# main_pcb.net
KiCad netlist of a schematic drawn in Altium Designer
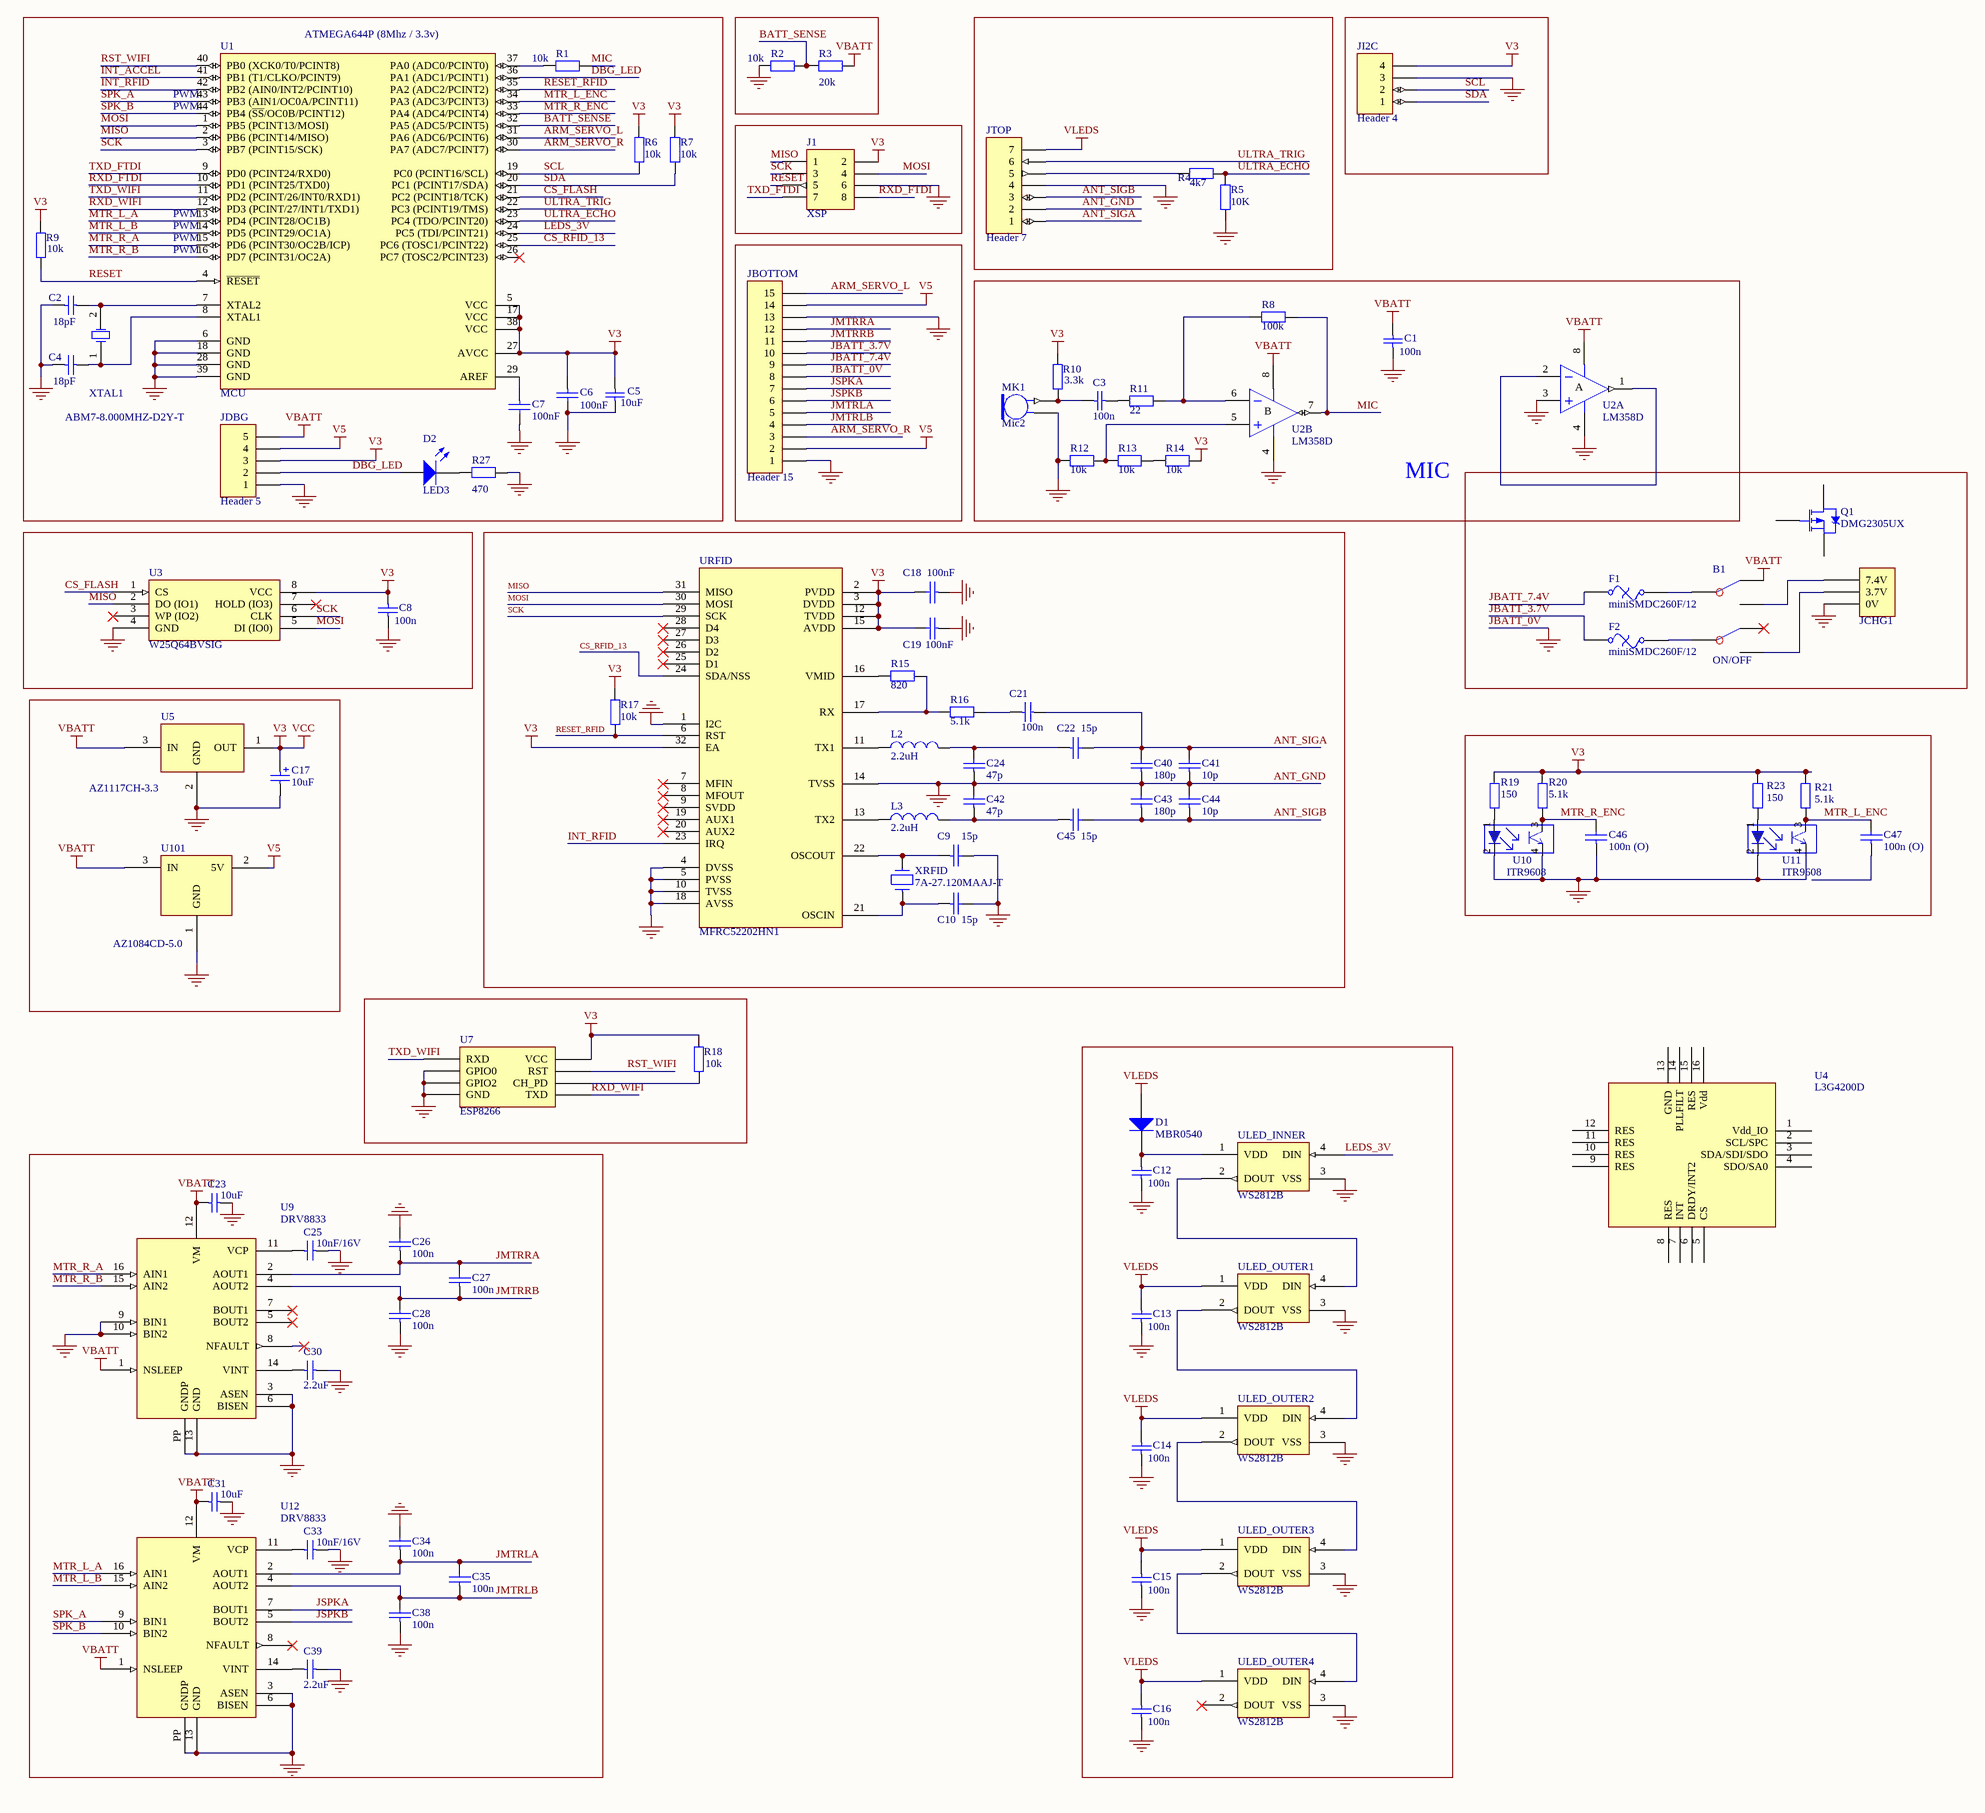
[diagram p0: main_pcb.SchDoc]

(export (version "E")
  (design (tool "Eeschema 10.0.6"))
  (components
    (comp (ref "B1") (value "ON/OFF") (footprint "KGPS22F03") (libsource (lib "*") (part "Component_1")))
    (comp (ref "C1")
      (value "100n")
      (footprint "CAPC1608N")
      (description "Capacitor")
      (libsource (lib "*") (part "Cap"))
    )
    (comp (ref "C2")
      (value "18pF")
      (footprint "CAPC1608N")
      (description "Capacitor")
      (libsource (lib "*") (part "Cap"))
    )
    (comp (ref "C3")
      (value "100n")
      (footprint "CAPC1608N")
      (description "Capacitor")
      (libsource (lib "") (part "Cap_1"))
    )
    (comp (ref "C4")
      (value "18pF")
      (footprint "CAPC1608N")
      (description "Capacitor")
      (libsource (lib "*") (part "Cap"))
    )
    (comp (ref "C5")
      (value "10uF")
      (footprint "CAPC3216L")
      (description "Capacitor")
      (libsource (lib "*") (part "Cap"))
    )
    (comp (ref "C6")
      (value "100nF")
      (footprint "CAPC1608N")
      (description "Capacitor")
      (libsource (lib "*") (part "CAP"))
    )
    (comp (ref "C7")
      (value "100nF")
      (footprint "CAPC1608N")
      (description "Capacitor")
      (libsource (lib "*") (part "CAP"))
    )
    (comp (ref "C8")
      (value "100n")
      (footprint "CAPC1608N")
      (description "Capacitor")
      (libsource (lib "*") (part "Cap"))
    )
    (comp (ref "C9")
      (value "15p")
      (footprint "CAPC1608N")
      (description "Capacitor")
      (libsource (lib "*") (part "CAP"))
    )
    (comp (ref "C10")
      (value "15p")
      (footprint "CAPC1608N")
      (description "Capacitor")
      (libsource (lib "*") (part "CAP"))
    )
    (comp (ref "C12")
      (value "100n")
      (footprint "CAPC1608N")
      (description "Capacitor")
      (libsource (lib "*") (part "Cap"))
    )
    (comp (ref "C13")
      (value "100n")
      (footprint "CAPC1608N")
      (description "Capacitor")
      (libsource (lib "*") (part "Cap"))
    )
    (comp (ref "C14")
      (value "100n")
      (footprint "CAPC1608N")
      (description "Capacitor")
      (libsource (lib "*") (part "Cap"))
    )
    (comp (ref "C15")
      (value "100n")
      (footprint "CAPC1608N")
      (description "Capacitor")
      (libsource (lib "*") (part "Cap"))
    )
    (comp (ref "C16")
      (value "100n")
      (footprint "CAPC1608N")
      (description "Capacitor")
      (libsource (lib "*") (part "Cap"))
    )
    (comp (ref "C17")
      (value "10uF")
      (footprint "CAPC2012N")
      (description "Polarized Capacitor (Axial)")
      (libsource (lib "*") (part "Cap Pol2"))
    )
    (comp (ref "C18")
      (value "100nF")
      (footprint "CAPC1608N")
      (description "Capacitor")
      (libsource (lib "*") (part "CAP"))
    )
    (comp (ref "C19")
      (value "100nF")
      (footprint "CAPC1608N")
      (description "Capacitor")
      (libsource (lib "*") (part "CAP"))
    )
    (comp (ref "C21")
      (value "100n")
      (footprint "CAPC1608N")
      (description "Capacitor")
      (libsource (lib "*") (part "Cap"))
    )
    (comp (ref "C22")
      (value "15p")
      (footprint "CAPC1608N")
      (description "Capacitor")
      (libsource (lib "*") (part "CAP"))
    )
    (comp (ref "C23")
      (value "10uF")
      (footprint "CAPC3216L")
      (description "Capacitor")
      (libsource (lib "*") (part "Cap"))
    )
    (comp (ref "C24")
      (value "47p")
      (footprint "CAPC1608N")
      (description "Capacitor")
      (libsource (lib "*") (part "CAP"))
    )
    (comp (ref "C25")
      (value "10nF/16V")
      (footprint "CAPC2012N")
      (description "Capacitor")
      (libsource (lib "*") (part "Cap"))
    )
    (comp (ref "C26")
      (value "100n")
      (footprint "CAPC1608N")
      (description "Capacitor")
      (libsource (lib "*") (part "CAP"))
    )
    (comp (ref "C27")
      (value "100n")
      (footprint "CAPC1608N")
      (description "Capacitor")
      (libsource (lib "*") (part "CAP"))
    )
    (comp (ref "C28")
      (value "100n")
      (footprint "CAPC1608N")
      (description "Capacitor")
      (libsource (lib "*") (part "CAP"))
    )
    (comp (ref "C30")
      (value "2.2uF")
      (footprint "CAPC2012N")
      (description "Capacitor")
      (libsource (lib "*") (part "Cap"))
    )
    (comp (ref "C31")
      (value "10uF")
      (footprint "CAPC3216L")
      (description "Capacitor")
      (libsource (lib "*") (part "Cap"))
    )
    (comp (ref "C33")
      (value "10nF/16V")
      (footprint "CAPC2012N")
      (description "Capacitor")
      (libsource (lib "*") (part "Cap"))
    )
    (comp (ref "C34")
      (value "100n")
      (footprint "CAPC1608N")
      (description "Capacitor")
      (libsource (lib "*") (part "CAP"))
    )
    (comp (ref "C35")
      (value "100n")
      (footprint "CAPC1608N")
      (description "Capacitor")
      (libsource (lib "*") (part "CAP"))
    )
    (comp (ref "C38")
      (value "100n")
      (footprint "CAPC1608N")
      (description "Capacitor")
      (libsource (lib "*") (part "CAP"))
    )
    (comp (ref "C39")
      (value "2.2uF")
      (footprint "CAPC2012N")
      (description "Capacitor")
      (libsource (lib "*") (part "Cap"))
    )
    (comp (ref "C40")
      (value "180p")
      (footprint "CAPC1608N")
      (description "Capacitor")
      (libsource (lib "*") (part "CAP"))
    )
    (comp (ref "C41")
      (value "10p")
      (footprint "CAPC1608N")
      (description "Capacitor")
      (libsource (lib "*") (part "CAP"))
    )
    (comp (ref "C42")
      (value "47p")
      (footprint "CAPC1608N")
      (description "Capacitor")
      (libsource (lib "*") (part "CAP"))
    )
    (comp (ref "C43")
      (value "180p")
      (footprint "CAPC1608N")
      (description "Capacitor")
      (libsource (lib "*") (part "CAP"))
    )
    (comp (ref "C44")
      (value "10p")
      (footprint "CAPC1608N")
      (description "Capacitor")
      (libsource (lib "*") (part "CAP"))
    )
    (comp (ref "C45")
      (value "15p")
      (footprint "CAPC1608N")
      (description "Capacitor")
      (libsource (lib "*") (part "CAP"))
    )
    (comp (ref "C46")
      (value "100n (O)")
      (footprint "CAPC1608N")
      (description "Capacitor")
      (libsource (lib "*") (part "CAP"))
    )
    (comp (ref "C47")
      (value "100n (O)")
      (footprint "CAPC1608N")
      (description "Capacitor")
      (libsource (lib "*") (part "CAP"))
    )
    (comp (ref "D1")
      (value "MBR0540")
      (footprint "SOD123/X.85")
      (description "Default Diode")
      (libsource (lib "Miscellaneous Devices") (part "Diode"))
    )
    (comp (ref "D2")
      (value "LED3")
      (footprint "CAPC1608N")
      (description "Typical BLUE SiC LED")
      (libsource (lib "Miscellaneous Devices") (part "LED3"))
    )
    (comp (ref "F1")
      (value "miniSMDC260F/12")
      (footprint "miniSMDC260F/12")
      (description "Thermal Fuse")
      (libsource (lib "Miscellaneous Devices") (part "Fuse Thermal"))
    )
    (comp (ref "F2")
      (value "miniSMDC260F/12")
      (footprint "miniSMDC260F/12")
      (description "Thermal Fuse")
      (libsource (lib "Miscellaneous Devices") (part "Fuse Thermal"))
    )
    (comp (ref "J1")
      (value "XSP")
      (footprint "HDR2X4H")
      (description "Header, 4-Pin, Dual row, Right Angle")
      (libsource (lib "Miscellaneous Connectors") (part "Header 4X2H"))
    )
    (comp (ref "JBOTTOM")
      (value "Header 15")
      (footprint "B15B-XH-A")
      (description "Header, 15-Pin")
      (libsource (lib "Miscellaneous Connectors") (part "Header 15"))
    )
    (comp (ref "JCHG1")
      (value "Charger")
      (footprint "S3B-XH-A(LF)(SN)")
      (libsource (lib "components") (part "BATTCON"))
    )
    (comp (ref "JDBG")
      (value "Header 5")
      (footprint "HDR1X5")
      (description "Header, 5-Pin")
      (libsource (lib "Miscellaneous Connectors") (part "Header 5"))
    )
    (comp (ref "JI2C")
      (value "Header 4")
      (footprint "HDR1X4")
      (description "Header, 4-Pin")
      (libsource (lib "Miscellaneous Connectors") (part "Header 4"))
    )
    (comp (ref "JTOP")
      (value "Header 7")
      (footprint "S7B-XH-A")
      (description "Header, 7-Pin")
      (libsource (lib "Miscellaneous Connectors") (part "Header 7"))
    )
    (comp (ref "L2")
      (value "2.2uH")
      (footprint "INDC1608N")
      (description "Inductor")
      (libsource (lib "Miscellaneous Devices") (part "Inductor"))
    )
    (comp (ref "L3")
      (value "2.2uH")
      (footprint "INDC1608N")
      (description "Inductor")
      (libsource (lib "Miscellaneous Devices") (part "Inductor"))
    )
    (comp (ref "MK1")
      (value "Mic2")
      (footprint "electret_6mm")
      (description "Microphone")
      (libsource (lib "*") (part "Mic2"))
    )
    (comp (ref "Q1")
      (value "DMG2305UX")
      (footprint "DMG2305UX-13")
      (libsource (lib "components") (part "DMG2305UX"))
    )
    (comp (ref "R1")
      (value "10k")
      (footprint "RESC1608N")
      (description "Resistor")
      (libsource (lib "") (part "Res2_2"))
    )
    (comp (ref "R2")
      (value "10k")
      (footprint "RESC1608N")
      (description "Resistor")
      (libsource (lib "") (part "Res2_2"))
    )
    (comp (ref "R3")
      (value "20k")
      (footprint "RESC1608N")
      (description "Resistor")
      (libsource (lib "") (part "Res2_2"))
    )
    (comp (ref "R4")
      (value "4k7")
      (footprint "RESC1608N")
      (description "Resistor")
      (fields (field (name "Comment") "10k"))
      (libsource (lib "") (part "Res2_3"))
    )
    (comp (ref "R5")
      (value "10K")
      (footprint "RESC1608N")
      (description "Resistor")
      (libsource (lib "") (part "Res2_1"))
    )
    (comp (ref "R6")
      (value "10k")
      (footprint "RESC1608N")
      (description "Resistor")
      (libsource (lib "*") (part "Res2"))
    )
    (comp (ref "R7")
      (value "10k")
      (footprint "RESC1608N")
      (description "Resistor")
      (libsource (lib "*") (part "Res2"))
    )
    (comp (ref "R8")
      (value "100k")
      (footprint "RESC1608N")
      (description "Resistor")
      (libsource (lib "") (part "Res2_2"))
    )
    (comp (ref "R9")
      (value "10k")
      (footprint "RESC1608N")
      (description "Resistor")
      (libsource (lib "") (part "Res2_1"))
    )
    (comp (ref "R10")
      (value "3.3k")
      (footprint "RESC1608N")
      (description "Resistor")
      (libsource (lib "") (part "Res2_1"))
    )
    (comp (ref "R11")
      (value "22")
      (footprint "RESC1608N")
      (description "Resistor")
      (libsource (lib "") (part "Res2_2"))
    )
    (comp (ref "R12")
      (value "10k")
      (footprint "RESC1608N")
      (description "Resistor")
      (libsource (lib "") (part "Res2_2"))
    )
    (comp (ref "R13")
      (value "10k")
      (footprint "RESC1608N")
      (description "Resistor")
      (libsource (lib "") (part "Res2_2"))
    )
    (comp (ref "R14")
      (value "10k")
      (footprint "RESC1608N")
      (description "Resistor")
      (libsource (lib "") (part "Res2_2"))
    )
    (comp (ref "R15")
      (value "820")
      (footprint "RESC1608N")
      (description "Resistor")
      (libsource (lib "") (part "Res2_3"))
    )
    (comp (ref "R16")
      (value "5.1k")
      (footprint "RESC1608N")
      (description "Resistor")
      (libsource (lib "") (part "Res2_3"))
    )
    (comp (ref "R17")
      (value "10k")
      (footprint "RESC1608N")
      (description "Resistor")
      (libsource (lib "") (part "Res2_1"))
    )
    (comp (ref "R18")
      (value "10k")
      (footprint "RESC1608N")
      (description "Resistor")
      (libsource (lib "") (part "Res2_3"))
    )
    (comp (ref "R19")
      (value "150")
      (footprint "RESC1608N")
      (description "Resistor")
      (fields (field (name "Comment") "1K"))
      (libsource (lib "*") (part "Res2"))
    )
    (comp (ref "R20")
      (value "5.1k")
      (footprint "RESC1608N")
      (description "Resistor")
      (libsource (lib "*") (part "Res2"))
    )
    (comp (ref "R21")
      (value "5.1k")
      (footprint "RESC1608N")
      (description "Resistor")
      (libsource (lib "*") (part "Res2"))
    )
    (comp (ref "R23")
      (value "150")
      (footprint "RESC1608N")
      (description "Resistor")
      (fields (field (name "Comment") "1K"))
      (libsource (lib "*") (part "Res2"))
    )
    (comp (ref "R27")
      (value "470")
      (footprint "RESC1608N")
      (description "Resistor")
      (libsource (lib "") (part "Res2_2"))
    )
    (comp (ref "U1")
      (value "MCU")
      (footprint "atmega644p")
      (description "8-bit AVR Microcontroller, 2.7-5.5V, 20MHz, 64KB Flash, 2KB EEPROM, 4KB SRAM, 44-pin TQFP")
      (libsource (lib "*") (part "ATmega644-20AU"))
    )
    (comp (ref "U2")
      (value "LM358D")
      (footprint "LM358D")
      (description "Dual Operational Amplifier")
      (libsource (lib "TI Operational Amplifier") (part "LM358D"))
    )
    (comp (ref "U3")
      (value "W25Q64BVSIG")
      (footprint "W25Q64BVSIG")
      (libsource (lib "components") (part "W25Q64BVSIG"))
    )
    (comp (ref "U4") (value "L3G4200D") (libsource (lib "components") (part "L3G4200D")))
    (comp (ref "U5") (value "AZ1117CH-3.3") (footprint "SOT223") (libsource (lib "*") (part "LM1117")))
    (comp (ref "U7") (value "ESP8266") (footprint "ESP8266") (libsource (lib "components") (part "ESP8266")))
    (comp (ref "U9") (value "DRV8833") (footprint "DRV8833") (libsource (lib "components") (part "DRV8833")))
    (comp (ref "U10") (value "ITR9608") (footprint "ITR9608") (libsource (lib "*") (part "ITR9608")))
    (comp (ref "U11") (value "ITR9608") (footprint "ITR9608") (libsource (lib "*") (part "ITR9608")))
    (comp (ref "U12") (value "DRV8833") (footprint "DRV8833") (libsource (lib "components") (part "DRV8833")))
    (comp (ref "U101")
      (value "AZ1084CD-5.0")
      (footprint "AZ1084CD-5.0")
      (libsource (lib "components") (part "AZ1084CD-5.0"))
    )
    (comp (ref "ULED_INNER")
      (value "WS2812B")
      (footprint "WS2812B")
      (libsource (lib "components") (part "WS2812B"))
    )
    (comp (ref "ULED_OUTER1")
      (value "WS2812B")
      (footprint "WS2812B")
      (libsource (lib "components") (part "WS2812B"))
    )
    (comp (ref "ULED_OUTER2")
      (value "WS2812B")
      (footprint "WS2812B")
      (libsource (lib "components") (part "WS2812B"))
    )
    (comp (ref "ULED_OUTER3")
      (value "WS2812B")
      (footprint "WS2812B")
      (libsource (lib "components") (part "WS2812B"))
    )
    (comp (ref "ULED_OUTER4")
      (value "WS2812B")
      (footprint "WS2812B")
      (libsource (lib "components") (part "WS2812B"))
    )
    (comp (ref "URFID")
      (value "MFRC52202HN1")
      (footprint "MFRC52202HN1")
      (libsource (lib "components") (part "MFRC52202HN1"))
    )
    (comp (ref "XRFID")
      (value "7A-27.120MAAJ-T")
      (footprint "XTAL")
      (libsource (lib "*") (part "Tm08B.S01_12M_42"))
    )
    (comp (ref "XTAL1")
      (value "ABM7-8.000MHZ-D2Y-T")
      (footprint "XTAL")
      (libsource (lib "components") (part "ABM7-8.000MHZ-D2Y-T"))
    )
  )
  (nets
    (net (code "1") (name "/ANT_SIGA") (class "Default")
      (node (ref "C21") (pin "2") (pinfunction "2_2") (pintype "passive"))
      (node (ref "C22") (pin "2") (pinfunction "2_2") (pintype "passive"))
      (node (ref "C40") (pin "2") (pinfunction "2_2") (pintype "passive"))
      (node (ref "C41") (pin "2") (pinfunction "2_2") (pintype "passive"))
      (node (ref "JTOP") (pin "1") (pinfunction "1_1") (pintype "bidirectional"))
    )
    (net (code "2") (name "/ANT_SIGB") (class "Default")
      (node (ref "C43") (pin "1") (pinfunction "1_1") (pintype "passive"))
      (node (ref "C44") (pin "1") (pinfunction "1_1") (pintype "passive"))
      (node (ref "C45") (pin "2") (pinfunction "2_2") (pintype "passive"))
      (node (ref "JTOP") (pin "3") (pinfunction "3_3") (pintype "bidirectional"))
    )
    (net (code "3") (name "/ARM_SERVO_L") (class "Default")
      (node (ref "JBOTTOM") (pin "15") (pinfunction "15_15") (pintype "passive"))
      (node (ref "U1") (pin "31") (pinfunction "PA6_(ADC6/PCINT6)_31") (pintype "bidirectional"))
    )
    (net (code "4") (name "/ARM_SERVO_R") (class "Default")
      (node (ref "JBOTTOM") (pin "3") (pinfunction "3_3") (pintype "passive"))
      (node (ref "U1") (pin "30") (pinfunction "PA7_(ADC7/PCINT7)_30") (pintype "bidirectional"))
    )
    (net (code "5") (name "/BATT_SENSE") (class "Default")
      (node (ref "R2") (pin "2") (pinfunction "2_2") (pintype "passive"))
      (node (ref "R3") (pin "1") (pinfunction "1_1") (pintype "passive"))
      (node (ref "U1") (pin "32") (pinfunction "PA5_(ADC5/PCINT5)_32") (pintype "bidirectional"))
    )
    (net (code "6") (name "/CS_FLASH") (class "Default")
      (node (ref "U1") (pin "21") (pinfunction "PC2_(PCINT18/TCK)_21") (pintype "bidirectional"))
      (node (ref "U3") (pin "1") (pinfunction "CS_1") (pintype "input"))
    )
    (net (code "7") (name "/CS_RFID_13") (class "Default")
      (node (ref "U1") (pin "25") (pinfunction "PC6_(TOSC1/PCINT22)_25") (pintype "bidirectional"))
      (node (ref "URFID") (pin "24") (pinfunction "SDA/NSS_24") (pintype "passive"))
    )
    (net (code "8") (name "/DBG_LED") (class "Default")
      (node (ref "D2") (pin "1") (pinfunction "A_1") (pintype "passive"))
      (node (ref "JDBG") (pin "2") (pinfunction "2_2") (pintype "passive"))
      (node (ref "U1") (pin "36") (pinfunction "PA1_(ADC1/PCINT1)_36") (pintype "bidirectional"))
    )
    (net (code "9") (name "/INT_ACCEL") (class "Default")
      (node (ref "U1") (pin "41") (pinfunction "PB1_(T1/CLKO/PCINT9)_41") (pintype "bidirectional"))
    )
    (net (code "10") (name "/INT_RFID") (class "Default")
      (node (ref "U1") (pin "42") (pinfunction "PB2_(AIN0/INT2/PCINT10)_42") (pintype "bidirectional"))
      (node (ref "URFID") (pin "23") (pinfunction "IRQ_23") (pintype "passive"))
    )
    (net (code "11") (name "/JBATT_3.7V") (class "Default")
      (node (ref "F2") (pin "1") (pinfunction "1_1") (pintype "passive"))
      (node (ref "JBOTTOM") (pin "10") (pinfunction "10_10") (pintype "passive"))
    )
    (net (code "12") (name "/JBATT_7.4V") (class "Default")
      (node (ref "F1") (pin "1") (pinfunction "1_1") (pintype "passive"))
      (node (ref "JBOTTOM") (pin "9") (pinfunction "9_9") (pintype "passive"))
    )
    (net (code "13") (name "/JMTRLA") (class "Default")
      (node (ref "C34") (pin "1") (pinfunction "1_1") (pintype "passive"))
      (node (ref "C35") (pin "2") (pinfunction "2_2") (pintype "passive"))
      (node (ref "JBOTTOM") (pin "5") (pinfunction "5_5") (pintype "passive"))
      (node (ref "U12") (pin "2") (pinfunction "AOUT1_2") (pintype "power_in"))
    )
    (net (code "14") (name "/JMTRLB") (class "Default")
      (node (ref "C35") (pin "1") (pinfunction "1_1") (pintype "passive"))
      (node (ref "C38") (pin "2") (pinfunction "2_2") (pintype "passive"))
      (node (ref "JBOTTOM") (pin "4") (pinfunction "4_4") (pintype "passive"))
      (node (ref "U12") (pin "4") (pinfunction "AOUT2_4") (pintype "power_in"))
    )
    (net (code "15") (name "/JMTRRA") (class "Default")
      (node (ref "C26") (pin "1") (pinfunction "1_1") (pintype "passive"))
      (node (ref "C27") (pin "2") (pinfunction "2_2") (pintype "passive"))
      (node (ref "JBOTTOM") (pin "12") (pinfunction "12_12") (pintype "passive"))
      (node (ref "U9") (pin "2") (pinfunction "AOUT1_2") (pintype "power_in"))
    )
    (net (code "16") (name "/JMTRRB") (class "Default")
      (node (ref "C27") (pin "1") (pinfunction "1_1") (pintype "passive"))
      (node (ref "C28") (pin "2") (pinfunction "2_2") (pintype "passive"))
      (node (ref "JBOTTOM") (pin "11") (pinfunction "11_11") (pintype "passive"))
      (node (ref "U9") (pin "4") (pinfunction "AOUT2_4") (pintype "power_in"))
    )
    (net (code "17") (name "/JSPKA") (class "Default")
      (node (ref "JBOTTOM") (pin "7") (pinfunction "7_7") (pintype "passive"))
      (node (ref "U12") (pin "7") (pinfunction "BOUT1_7") (pintype "power_in"))
    )
    (net (code "18") (name "/JSPKB") (class "Default")
      (node (ref "JBOTTOM") (pin "6") (pinfunction "6_6") (pintype "passive"))
      (node (ref "U12") (pin "5") (pinfunction "BOUT2_5") (pintype "power_in"))
    )
    (net (code "19") (name "/LEDS_3V") (class "Default")
      (node (ref "U1") (pin "24") (pinfunction "PC5_(TDI/PCINT21)_24") (pintype "bidirectional"))
      (node (ref "ULED_INNER") (pin "4") (pinfunction "DIN_4") (pintype "input"))
    )
    (net (code "20") (name "/MIC") (class "Default")
      (node (ref "R1") (pin "2") (pinfunction "2_2") (pintype "passive"))
      (node (ref "R8") (pin "2") (pinfunction "2_2") (pintype "passive"))
      (node (ref "U2") (pin "7") (pinfunction "OUT_7") (pintype "bidirectional"))
    )
    (net (code "21") (name "/MISO") (class "Default")
      (node (ref "J1") (pin "1") (pinfunction "1_1") (pintype "passive"))
      (node (ref "U1") (pin "2") (pinfunction "PB6_(PCINT14/MISO)_2") (pintype "bidirectional"))
      (node (ref "U3") (pin "2") (pinfunction "DO_(IO1)_2") (pintype "passive"))
      (node (ref "URFID") (pin "31") (pinfunction "MISO_31") (pintype "passive"))
    )
    (net (code "22") (name "/MOSI") (class "Default")
      (node (ref "J1") (pin "4") (pinfunction "4_4") (pintype "passive"))
      (node (ref "U1") (pin "1") (pinfunction "PB5_(PCINT13/MOSI)_1") (pintype "bidirectional"))
      (node (ref "U3") (pin "5") (pinfunction "DI_(IO0)_5") (pintype "passive"))
      (node (ref "URFID") (pin "30") (pinfunction "MOSI_30") (pintype "passive"))
    )
    (net (code "23") (name "/MTR_L_A") (class "Default")
      (node (ref "U1") (pin "13") (pinfunction "PD4_(PCINT28/OC1B)_13") (pintype "bidirectional"))
      (node (ref "U12") (pin "16") (pinfunction "AIN1_16") (pintype "input"))
    )
    (net (code "24") (name "/MTR_L_B") (class "Default")
      (node (ref "U1") (pin "14") (pinfunction "PD5_(PCINT29/OC1A)_14") (pintype "bidirectional"))
      (node (ref "U12") (pin "15") (pinfunction "AIN2_15") (pintype "input"))
    )
    (net (code "25") (name "/MTR_L_ENC") (class "Default")
      (node (ref "C47") (pin "2") (pinfunction "2_2") (pintype "passive"))
      (node (ref "R21") (pin "1") (pinfunction "1_1") (pintype "passive"))
      (node (ref "U1") (pin "34") (pinfunction "PA3_(ADC3/PCINT3)_34") (pintype "bidirectional"))
      (node (ref "U11") (pin "3") (pinfunction "COLLECTOR_3") (pintype "passive"))
    )
    (net (code "26") (name "/MTR_R_A") (class "Default")
      (node (ref "U1") (pin "15") (pinfunction "PD6_(PCINT30/OC2B/ICP)_15") (pintype "bidirectional"))
      (node (ref "U9") (pin "16") (pinfunction "AIN1_16") (pintype "input"))
    )
    (net (code "27") (name "/MTR_R_B") (class "Default")
      (node (ref "U1") (pin "16") (pinfunction "PD7_(PCINT31/OC2A)_16") (pintype "bidirectional"))
      (node (ref "U9") (pin "15") (pinfunction "AIN2_15") (pintype "input"))
    )
    (net (code "28") (name "/MTR_R_ENC") (class "Default")
      (node (ref "C46") (pin "2") (pinfunction "2_2") (pintype "passive"))
      (node (ref "R20") (pin "1") (pinfunction "1_1") (pintype "passive"))
      (node (ref "U1") (pin "33") (pinfunction "PA4_(ADC4/PCINT4)_33") (pintype "bidirectional"))
      (node (ref "U10") (pin "3") (pinfunction "COLLECTOR_3") (pintype "passive"))
    )
    (net (code "29") (name "/RESET") (class "Default")
      (node (ref "J1") (pin "5") (pinfunction "5_5") (pintype "output"))
      (node (ref "R9") (pin "2") (pinfunction "2_2") (pintype "passive"))
      (node (ref "U1") (pin "4") (pinfunction "~{RESET}_4") (pintype "input"))
    )
    (net (code "30") (name "/RESET_RFID") (class "Default")
      (node (ref "R17") (pin "2") (pinfunction "2_2") (pintype "passive"))
      (node (ref "U1") (pin "35") (pinfunction "PA2_(ADC2/PCINT2)_35") (pintype "bidirectional"))
      (node (ref "URFID") (pin "6") (pinfunction "RST_6") (pintype "passive"))
    )
    (net (code "31") (name "/RST_WIFI") (class "Default")
      (node (ref "U1") (pin "40") (pinfunction "PB0_(XCK0/T0/PCINT8)_40") (pintype "bidirectional"))
      (node (ref "U7") (pin "RST") (pinfunction "RST_RST") (pintype "passive"))
    )
    (net (code "32") (name "/RXD_FTDI") (class "Default")
      (node (ref "J1") (pin "8") (pinfunction "8_8") (pintype "passive"))
      (node (ref "U1") (pin "10") (pinfunction "PD1_(PCINT25/TXD0)_10") (pintype "bidirectional"))
    )
    (net (code "33") (name "/RXD_WIFI") (class "Default")
      (node (ref "U1") (pin "12") (pinfunction "PD3_(PCINT/27/INT1/TXD1)_12") (pintype "bidirectional"))
      (node (ref "U7") (pin "TXD") (pinfunction "TXD_TXD") (pintype "passive"))
    )
    (net (code "34") (name "/SCK") (class "Default")
      (node (ref "J1") (pin "3") (pinfunction "3_3") (pintype "passive"))
      (node (ref "U1") (pin "3") (pinfunction "PB7_(PCINT15/SCK)_3") (pintype "bidirectional"))
      (node (ref "U3") (pin "6") (pinfunction "CLK_6") (pintype "passive"))
      (node (ref "URFID") (pin "29") (pinfunction "SCK_29") (pintype "passive"))
    )
    (net (code "35") (name "/SCL") (class "Default")
      (node (ref "JI2C") (pin "2") (pinfunction "2_2") (pintype "bidirectional"))
      (node (ref "R6") (pin "1") (pinfunction "1_1") (pintype "passive"))
      (node (ref "U1") (pin "19") (pinfunction "PC0_(PCINT16/SCL)_19") (pintype "bidirectional"))
    )
    (net (code "36") (name "/SDA") (class "Default")
      (node (ref "JI2C") (pin "1") (pinfunction "1_1") (pintype "bidirectional"))
      (node (ref "R7") (pin "1") (pinfunction "1_1") (pintype "passive"))
      (node (ref "U1") (pin "20") (pinfunction "PC1_(PCINT17/SDA)_20") (pintype "bidirectional"))
    )
    (net (code "37") (name "/SPK_A") (class "Default")
      (node (ref "U1") (pin "43") (pinfunction "PB3_(AIN1/OC0A/PCINT11)_43") (pintype "bidirectional"))
      (node (ref "U12") (pin "9") (pinfunction "BIN1_9") (pintype "input"))
    )
    (net (code "38") (name "/SPK_B") (class "Default")
      (node (ref "U1") (pin "44") (pinfunction "PB4_(~{SS}/OC0B/PCINT12)_44") (pintype "bidirectional"))
      (node (ref "U12") (pin "10") (pinfunction "BIN2_10") (pintype "input"))
    )
    (net (code "39") (name "/TXD_FTDI") (class "Default")
      (node (ref "J1") (pin "7") (pinfunction "7_7") (pintype "passive"))
      (node (ref "U1") (pin "9") (pinfunction "PD0_(PCINT24/RXD0)_9") (pintype "bidirectional"))
    )
    (net (code "40") (name "/TXD_WIFI") (class "Default")
      (node (ref "U1") (pin "11") (pinfunction "PD2_(PCINT/26/INT0/RXD1)_11") (pintype "bidirectional"))
      (node (ref "U7") (pin "RXD") (pinfunction "RXD_RXD") (pintype "passive"))
    )
    (net (code "41") (name "/ULTRA_ECHO") (class "Default")
      (node (ref "R4") (pin "1") (pinfunction "1_1") (pintype "passive"))
      (node (ref "R5") (pin "1") (pinfunction "1_1") (pintype "passive"))
      (node (ref "U1") (pin "23") (pinfunction "PC4_(TDO/PCINT20)_23") (pintype "bidirectional"))
    )
    (net (code "42") (name "/ULTRA_TRIG") (class "Default")
      (node (ref "JTOP") (pin "6") (pinfunction "6_6") (pintype "input"))
      (node (ref "U1") (pin "22") (pinfunction "PC3_(PCINT19/TMS)_22") (pintype "bidirectional"))
    )
    (net (code "43") (name "GND") (class "Default")
      (node (ref "C1") (pin "2") (pinfunction "2_2") (pintype "passive"))
      (node (ref "C10") (pin "2") (pinfunction "2_2") (pintype "passive"))
      (node (ref "C12") (pin "2") (pinfunction "2_2") (pintype "passive"))
      (node (ref "C13") (pin "2") (pinfunction "2_2") (pintype "passive"))
      (node (ref "C14") (pin "2") (pinfunction "2_2") (pintype "passive"))
      (node (ref "C15") (pin "2") (pinfunction "2_2") (pintype "passive"))
      (node (ref "C16") (pin "2") (pinfunction "2_2") (pintype "passive"))
      (node (ref "C17") (pin "2") (pinfunction "2_2") (pintype "passive"))
      (node (ref "C18") (pin "1") (pinfunction "1_1") (pintype "passive"))
      (node (ref "C19") (pin "1") (pinfunction "1_1") (pintype "passive"))
      (node (ref "C2") (pin "1") (pinfunction "1_1") (pintype "passive"))
      (node (ref "C23") (pin "1") (pinfunction "1_1") (pintype "passive"))
      (node (ref "C24") (pin "1") (pinfunction "1_1") (pintype "passive"))
      (node (ref "C25") (pin "1") (pinfunction "1_1") (pintype "passive"))
      (node (ref "C26") (pin "2") (pinfunction "2_2") (pintype "passive"))
      (node (ref "C28") (pin "1") (pinfunction "1_1") (pintype "passive"))
      (node (ref "C30") (pin "1") (pinfunction "1_1") (pintype "passive"))
      (node (ref "C31") (pin "1") (pinfunction "1_1") (pintype "passive"))
      (node (ref "C33") (pin "1") (pinfunction "1_1") (pintype "passive"))
      (node (ref "C34") (pin "2") (pinfunction "2_2") (pintype "passive"))
      (node (ref "C38") (pin "1") (pinfunction "1_1") (pintype "passive"))
      (node (ref "C39") (pin "1") (pinfunction "1_1") (pintype "passive"))
      (node (ref "C4") (pin "1") (pinfunction "1_1") (pintype "passive"))
      (node (ref "C40") (pin "1") (pinfunction "1_1") (pintype "passive"))
      (node (ref "C41") (pin "1") (pinfunction "1_1") (pintype "passive"))
      (node (ref "C42") (pin "2") (pinfunction "2_2") (pintype "passive"))
      (node (ref "C43") (pin "2") (pinfunction "2_2") (pintype "passive"))
      (node (ref "C44") (pin "2") (pinfunction "2_2") (pintype "passive"))
      (node (ref "C46") (pin "1") (pinfunction "1_1") (pintype "passive"))
      (node (ref "C5") (pin "1") (pinfunction "1_1") (pintype "passive"))
      (node (ref "C6") (pin "2") (pinfunction "2_2") (pintype "passive"))
      (node (ref "C7") (pin "2") (pinfunction "2_2") (pintype "passive"))
      (node (ref "C8") (pin "2") (pinfunction "2_2") (pintype "passive"))
      (node (ref "C9") (pin "2") (pinfunction "2_2") (pintype "passive"))
      (node (ref "J1") (pin "6") (pinfunction "6_6") (pintype "passive"))
      (node (ref "JBOTTOM") (pin "1") (pinfunction "1_1") (pintype "passive"))
      (node (ref "JBOTTOM") (pin "13") (pinfunction "13_13") (pintype "passive"))
      (node (ref "JBOTTOM") (pin "8") (pinfunction "8_8") (pintype "passive"))
      (node (ref "JCHG1") (pin "1") (pinfunction "0V_1") (pintype "passive"))
      (node (ref "JDBG") (pin "1") (pinfunction "1_1") (pintype "passive"))
      (node (ref "JI2C") (pin "3") (pinfunction "3_3") (pintype "power_in"))
      (node (ref "JTOP") (pin "2") (pinfunction "2_2") (pintype "power_in"))
      (node (ref "JTOP") (pin "4") (pinfunction "4_4") (pintype "power_in"))
      (node (ref "MK1") (pin "2") (pinfunction "2_2") (pintype "power_in"))
      (node (ref "R12") (pin "1") (pinfunction "1_1") (pintype "passive"))
      (node (ref "R2") (pin "1") (pinfunction "1_1") (pintype "passive"))
      (node (ref "R27") (pin "2") (pinfunction "2_2") (pintype "passive"))
      (node (ref "R5") (pin "2") (pinfunction "2_2") (pintype "passive"))
      (node (ref "U1") (pin "18") (pinfunction "GND_18") (pintype "power_in"))
      (node (ref "U1") (pin "28") (pinfunction "GND_28") (pintype "power_in"))
      (node (ref "U1") (pin "39") (pinfunction "GND_39") (pintype "power_in"))
      (node (ref "U1") (pin "6") (pinfunction "GND_6") (pintype "power_in"))
      (node (ref "U10") (pin "2") (pinfunction "CATHODE_2") (pintype "passive"))
      (node (ref "U10") (pin "4") (pinfunction "ENITIER_4") (pintype "passive"))
      (node (ref "U101") (pin "1") (pinfunction "GND_1") (pintype "passive"))
      (node (ref "U11") (pin "2") (pinfunction "CATHODE_2") (pintype "passive"))
      (node (ref "U11") (pin "4") (pinfunction "ENITIER_4") (pintype "passive"))
      (node (ref "U12") (pin "13") (pinfunction "GND_13") (pintype "power_in"))
      (node (ref "U12") (pin "3") (pinfunction "ASEN_3") (pintype "power_in"))
      (node (ref "U12") (pin "6") (pinfunction "BISEN_6") (pintype "power_in"))
      (node (ref "U12") (pin "PP") (pinfunction "GNDP_PP") (pintype "power_in"))
      (node (ref "U2") (pin "3") (pinfunction "IN+_3") (pintype "passive"))
      (node (ref "U2") (pin "4") (pinfunction "V-_4") (pintype "power_in"))
      (node (ref "U3") (pin "4") (pinfunction "GND_4") (pintype "power_in"))
      (node (ref "U5") (pin "2") (pinfunction "GND_2") (pintype "passive"))
      (node (ref "U7") (pin "GND") (pinfunction "GND_GND") (pintype "passive"))
      (node (ref "U7") (pin "GPIO0") (pinfunction "GPIO0_GPIO0") (pintype "passive"))
      (node (ref "U7") (pin "GPIO2") (pinfunction "GPIO2_GPIO2") (pintype "passive"))
      (node (ref "U9") (pin "10") (pinfunction "BIN2_10") (pintype "input"))
      (node (ref "U9") (pin "13") (pinfunction "GND_13") (pintype "power_in"))
      (node (ref "U9") (pin "3") (pinfunction "ASEN_3") (pintype "power_in"))
      (node (ref "U9") (pin "6") (pinfunction "BISEN_6") (pintype "power_in"))
      (node (ref "U9") (pin "9") (pinfunction "BIN1_9") (pintype "input"))
      (node (ref "U9") (pin "PP") (pinfunction "GNDP_PP") (pintype "power_in"))
      (node (ref "ULED_INNER") (pin "3") (pinfunction "VSS_3") (pintype "power_in"))
      (node (ref "ULED_OUTER1") (pin "3") (pinfunction "VSS_3") (pintype "power_in"))
      (node (ref "ULED_OUTER2") (pin "3") (pinfunction "VSS_3") (pintype "power_in"))
      (node (ref "ULED_OUTER3") (pin "3") (pinfunction "VSS_3") (pintype "power_in"))
      (node (ref "ULED_OUTER4") (pin "3") (pinfunction "VSS_3") (pintype "power_in"))
      (node (ref "URFID") (pin "1") (pinfunction "I2C_1") (pintype "passive"))
      (node (ref "URFID") (pin "10") (pinfunction "TVSS_10") (pintype "passive"))
      (node (ref "URFID") (pin "14") (pinfunction "TVSS_14") (pintype "passive"))
      (node (ref "URFID") (pin "18") (pinfunction "AVSS_18") (pintype "passive"))
      (node (ref "URFID") (pin "4") (pinfunction "DVSS_4") (pintype "passive"))
      (node (ref "URFID") (pin "5") (pinfunction "PVSS_5") (pintype "passive"))
    )
    (net (code "44") (name "Net-(B1-Pad2)") (class "Default")
      (node (ref "B1") (pin "2") (pintype "passive"))
      (node (ref "F1") (pin "2") (pinfunction "2_2") (pintype "passive"))
    )
    (net (code "45") (name "Net-(B1-Pad5)") (class "Default")
      (node (ref "B1") (pin "5") (pintype "passive"))
      (node (ref "F2") (pin "2") (pinfunction "2_2") (pintype "passive"))
    )
    (net (code "46") (name "Net-(C3-Pad1)") (class "Default")
      (node (ref "C3") (pin "1") (pinfunction "1_1") (pintype "passive"))
      (node (ref "R11") (pin "1") (pinfunction "1_1") (pintype "passive"))
    )
    (net (code "47") (name "Net-(C3-Pad2)") (class "Default")
      (node (ref "C3") (pin "2") (pinfunction "2_2") (pintype "passive"))
      (node (ref "MK1") (pin "1") (pinfunction "1_1") (pintype "output"))
      (node (ref "R10") (pin "2") (pinfunction "2_2") (pintype "passive"))
    )
    (net (code "48") (name "Net-(C21-Pad1)") (class "Default")
      (node (ref "C21") (pin "1") (pinfunction "1_1") (pintype "passive"))
      (node (ref "R16") (pin "1") (pinfunction "1_1") (pintype "passive"))
    )
    (net (code "49") (name "Net-(C22-Pad1)") (class "Default")
      (node (ref "C22") (pin "1") (pinfunction "1_1") (pintype "passive"))
      (node (ref "C24") (pin "2") (pinfunction "2_2") (pintype "passive"))
      (node (ref "L2") (pin "2") (pinfunction "2_2") (pintype "passive"))
    )
    (net (code "50") (name "Net-(C42-Pad1)") (class "Default")
      (node (ref "C42") (pin "1") (pinfunction "1_1") (pintype "passive"))
      (node (ref "C45") (pin "1") (pinfunction "1_1") (pintype "passive"))
      (node (ref "L3") (pin "2") (pinfunction "2_2") (pintype "passive"))
    )
    (net (code "51") (name "Net-(D1-K)") (class "Default")
      (node (ref "C12") (pin "1") (pinfunction "1_1") (pintype "passive"))
      (node (ref "D1") (pin "1") (pinfunction "K_1") (pintype "passive"))
      (node (ref "ULED_INNER") (pin "1") (pinfunction "VDD_1") (pintype "power_in"))
    )
    (net (code "52") (name "Net-(D2-K)") (class "Default")
      (node (ref "D2") (pin "2") (pinfunction "K_2") (pintype "passive"))
      (node (ref "R27") (pin "1") (pinfunction "1_1") (pintype "passive"))
    )
    (net (code "53") (name "Net-(JCHG1-3.7V)") (class "Default")
      (node (ref "B1") (pin "6") (pintype "passive"))
      (node (ref "JCHG1") (pin "2") (pinfunction "3.7V_2") (pintype "passive"))
    )
    (net (code "54") (name "Net-(JCHG1-7.4V)") (class "Default")
      (node (ref "B1") (pin "1") (pintype "passive"))
      (node (ref "JCHG1") (pin "3") (pinfunction "7.4V_3") (pintype "passive"))
    )
    (net (code "55") (name "Net-(JTOP-Pad5)") (class "Default")
      (node (ref "JTOP") (pin "5") (pinfunction "5_5") (pintype "output"))
      (node (ref "R4") (pin "2") (pinfunction "2_2") (pintype "passive"))
    )
    (net (code "56") (name "Net-(R13-Pad2)") (class "Default")
      (node (ref "R13") (pin "2") (pinfunction "2_2") (pintype "passive"))
      (node (ref "R14") (pin "1") (pinfunction "1_1") (pintype "passive"))
    )
    (net (code "57") (name "Net-(R18-Pad2)") (class "Default")
      (node (ref "R18") (pin "2") (pinfunction "2_2") (pintype "passive"))
      (node (ref "U7") (pin "CH_PD") (pinfunction "CH_PD_CH_PD") (pintype "passive"))
    )
    (net (code "58") (name "Net-(U1-AREF)") (class "Default")
      (node (ref "C7") (pin "1") (pinfunction "1_1") (pintype "passive"))
      (node (ref "U1") (pin "29") (pinfunction "AREF_29") (pintype "passive"))
    )
    (net (code "59") (name "Net-(U1-PA0_(ADC0{slash}PCINT0))") (class "Default")
      (node (ref "R1") (pin "1") (pinfunction "1_1") (pintype "passive"))
      (node (ref "U1") (pin "37") (pinfunction "PA0_(ADC0/PCINT0)_37") (pintype "bidirectional"))
    )
    (net (code "60") (name "Net-(U1-XTAL1)") (class "Default")
      (node (ref "C4") (pin "2") (pinfunction "2_2") (pintype "passive"))
      (node (ref "U1") (pin "8") (pinfunction "XTAL1_8") (pintype "passive"))
      (node (ref "XTAL1") (pin "1") (pinfunction "OSC1_1") (pintype "passive"))
    )
    (net (code "61") (name "Net-(U1-XTAL2)") (class "Default")
      (node (ref "C2") (pin "2") (pinfunction "2_2") (pintype "passive"))
      (node (ref "U1") (pin "7") (pinfunction "XTAL2_7") (pintype "passive"))
      (node (ref "XTAL1") (pin "2") (pinfunction "OSC2_2") (pintype "passive"))
    )
    (net (code "62") (name "Net-(U2A-IN-)") (class "Default")
      (node (ref "U2") (pin "1") (pinfunction "OUT_1") (pintype "output"))
      (node (ref "U2") (pin "2") (pinfunction "IN-_2") (pintype "passive"))
    )
    (net (code "63") (name "Net-(U2B-IN+)") (class "Default")
      (node (ref "R12") (pin "2") (pinfunction "2_2") (pintype "passive"))
      (node (ref "R13") (pin "1") (pinfunction "1_1") (pintype "passive"))
      (node (ref "U2") (pin "5") (pinfunction "IN+_5") (pintype "passive"))
    )
    (net (code "64") (name "Net-(U2B-IN-)") (class "Default")
      (node (ref "R11") (pin "2") (pinfunction "2_2") (pintype "passive"))
      (node (ref "R8") (pin "1") (pinfunction "1_1") (pintype "passive"))
      (node (ref "U2") (pin "6") (pinfunction "IN-_6") (pintype "passive"))
    )
    (net (code "65") (name "Net-(U9-VCP)") (class "Default")
      (node (ref "C25") (pin "2") (pinfunction "2_2") (pintype "passive"))
      (node (ref "U9") (pin "11") (pinfunction "VCP_11") (pintype "power_in"))
    )
    (net (code "66") (name "Net-(U9-VINT)") (class "Default")
      (node (ref "C30") (pin "2") (pinfunction "2_2") (pintype "passive"))
      (node (ref "U9") (pin "14") (pinfunction "VINT_14") (pintype "power_in"))
    )
    (net (code "67") (name "Net-(U10-ANODE)") (class "Default")
      (node (ref "R19") (pin "1") (pinfunction "1_1") (pintype "passive"))
      (node (ref "U10") (pin "1") (pinfunction "ANODE_1") (pintype "passive"))
    )
    (net (code "68") (name "Net-(U11-ANODE)") (class "Default")
      (node (ref "R23") (pin "1") (pinfunction "1_1") (pintype "passive"))
      (node (ref "U11") (pin "1") (pinfunction "ANODE_1") (pintype "passive"))
    )
    (net (code "69") (name "Net-(U12-VCP)") (class "Default")
      (node (ref "C33") (pin "2") (pinfunction "2_2") (pintype "passive"))
      (node (ref "U12") (pin "11") (pinfunction "VCP_11") (pintype "power_in"))
    )
    (net (code "70") (name "Net-(U12-VINT)") (class "Default")
      (node (ref "C39") (pin "2") (pinfunction "2_2") (pintype "passive"))
      (node (ref "U12") (pin "14") (pinfunction "VINT_14") (pintype "power_in"))
    )
    (net (code "71") (name "Net-(ULED_INNER-DOUT)") (class "Default")
      (node (ref "ULED_INNER") (pin "2") (pinfunction "DOUT_2") (pintype "output"))
      (node (ref "ULED_OUTER1") (pin "4") (pinfunction "DIN_4") (pintype "input"))
    )
    (net (code "72") (name "Net-(ULED_OUTER1-DOUT)") (class "Default")
      (node (ref "ULED_OUTER1") (pin "2") (pinfunction "DOUT_2") (pintype "output"))
      (node (ref "ULED_OUTER2") (pin "4") (pinfunction "DIN_4") (pintype "input"))
    )
    (net (code "73") (name "Net-(ULED_OUTER2-DOUT)") (class "Default")
      (node (ref "ULED_OUTER2") (pin "2") (pinfunction "DOUT_2") (pintype "output"))
      (node (ref "ULED_OUTER3") (pin "4") (pinfunction "DIN_4") (pintype "input"))
    )
    (net (code "74") (name "Net-(ULED_OUTER3-DOUT)") (class "Default")
      (node (ref "ULED_OUTER3") (pin "2") (pinfunction "DOUT_2") (pintype "output"))
      (node (ref "ULED_OUTER4") (pin "4") (pinfunction "DIN_4") (pintype "input"))
    )
    (net (code "75") (name "Net-(URFID-OSCIN)") (class "Default")
      (node (ref "C10") (pin "1") (pinfunction "1_1") (pintype "passive"))
      (node (ref "URFID") (pin "21") (pinfunction "OSCIN_21") (pintype "passive"))
      (node (ref "XRFID") (pin "1") (pintype "passive"))
    )
    (net (code "76") (name "Net-(URFID-OSCOUT)") (class "Default")
      (node (ref "C9") (pin "1") (pinfunction "1_1") (pintype "passive"))
      (node (ref "URFID") (pin "22") (pinfunction "OSCOUT_22") (pintype "passive"))
      (node (ref "XRFID") (pin "2") (pintype "passive"))
    )
    (net (code "77") (name "Net-(URFID-RX)") (class "Default")
      (node (ref "R15") (pin "1") (pinfunction "1_1") (pintype "passive"))
      (node (ref "R16") (pin "2") (pinfunction "2_2") (pintype "passive"))
      (node (ref "URFID") (pin "17") (pinfunction "RX_17") (pintype "passive"))
    )
    (net (code "78") (name "Net-(URFID-TX1)") (class "Default")
      (node (ref "L2") (pin "1") (pinfunction "1_1") (pintype "passive"))
      (node (ref "URFID") (pin "11") (pinfunction "TX1_11") (pintype "passive"))
    )
    (net (code "79") (name "Net-(URFID-TX2)") (class "Default")
      (node (ref "L3") (pin "1") (pinfunction "1_1") (pintype "passive"))
      (node (ref "URFID") (pin "13") (pinfunction "TX2_13") (pintype "passive"))
    )
    (net (code "80") (name "Net-(URFID-VMID)") (class "Default")
      (node (ref "R15") (pin "2") (pinfunction "2_2") (pintype "passive"))
      (node (ref "URFID") (pin "16") (pinfunction "VMID_16") (pintype "passive"))
    )
    (net (code "81") (name "V3") (class "Default")
      (node (ref "C17") (pin "1") (pinfunction "1_1") (pintype "passive"))
      (node (ref "C18") (pin "2") (pinfunction "2_2") (pintype "passive"))
      (node (ref "C19") (pin "2") (pinfunction "2_2") (pintype "passive"))
      (node (ref "C5") (pin "2") (pinfunction "2_2") (pintype "passive"))
      (node (ref "C6") (pin "1") (pinfunction "1_1") (pintype "passive"))
      (node (ref "C8") (pin "1") (pinfunction "1_1") (pintype "passive"))
      (node (ref "J1") (pin "2") (pinfunction "2_2") (pintype "passive"))
      (node (ref "JDBG") (pin "3") (pinfunction "3_3") (pintype "passive"))
      (node (ref "JI2C") (pin "4") (pinfunction "4_4") (pintype "power_in"))
      (node (ref "R10") (pin "1") (pinfunction "1_1") (pintype "passive"))
      (node (ref "R14") (pin "2") (pinfunction "2_2") (pintype "passive"))
      (node (ref "R17") (pin "1") (pinfunction "1_1") (pintype "passive"))
      (node (ref "R18") (pin "1") (pinfunction "1_1") (pintype "passive"))
      (node (ref "R19") (pin "2") (pinfunction "2_2") (pintype "passive"))
      (node (ref "R20") (pin "2") (pinfunction "2_2") (pintype "passive"))
      (node (ref "R21") (pin "2") (pinfunction "2_2") (pintype "passive"))
      (node (ref "R23") (pin "2") (pinfunction "2_2") (pintype "passive"))
      (node (ref "R6") (pin "2") (pinfunction "2_2") (pintype "passive"))
      (node (ref "R7") (pin "2") (pinfunction "2_2") (pintype "passive"))
      (node (ref "R9") (pin "1") (pinfunction "1_1") (pintype "passive"))
      (node (ref "U1") (pin "17") (pinfunction "VCC_17") (pintype "power_in"))
      (node (ref "U1") (pin "27") (pinfunction "AVCC_27") (pintype "power_in"))
      (node (ref "U1") (pin "38") (pinfunction "VCC_38") (pintype "power_in"))
      (node (ref "U1") (pin "5") (pinfunction "VCC_5") (pintype "power_in"))
      (node (ref "U3") (pin "8") (pinfunction "VCC_8") (pintype "power_in"))
      (node (ref "U5") (pin "1") (pinfunction "OUT_1") (pintype "passive"))
      (node (ref "U7") (pin "VCC") (pinfunction "VCC_VCC") (pintype "passive"))
      (node (ref "URFID") (pin "12") (pinfunction "TVDD_12") (pintype "passive"))
      (node (ref "URFID") (pin "15") (pinfunction "AVDD_15") (pintype "passive"))
      (node (ref "URFID") (pin "2") (pinfunction "PVDD_2") (pintype "passive"))
      (node (ref "URFID") (pin "3") (pinfunction "DVDD_3") (pintype "passive"))
      (node (ref "URFID") (pin "32") (pinfunction "EA_32") (pintype "passive"))
    )
    (net (code "82") (name "V5") (class "Default")
      (node (ref "JBOTTOM") (pin "14") (pinfunction "14_14") (pintype "passive"))
      (node (ref "JBOTTOM") (pin "2") (pinfunction "2_2") (pintype "passive"))
      (node (ref "JDBG") (pin "4") (pinfunction "4_4") (pintype "passive"))
      (node (ref "U101") (pin "2") (pinfunction "5V_2") (pintype "passive"))
    )
    (net (code "83") (name "VBATT") (class "Default")
      (node (ref "B1") (pin "3") (pintype "passive"))
      (node (ref "C1") (pin "1") (pinfunction "1_1") (pintype "passive"))
      (node (ref "C23") (pin "2") (pinfunction "2_2") (pintype "passive"))
      (node (ref "C31") (pin "2") (pinfunction "2_2") (pintype "passive"))
      (node (ref "JDBG") (pin "5") (pinfunction "5_5") (pintype "passive"))
      (node (ref "R3") (pin "2") (pinfunction "2_2") (pintype "passive"))
      (node (ref "U101") (pin "3") (pinfunction "IN_3") (pintype "passive"))
      (node (ref "U12") (pin "1") (pinfunction "NSLEEP_1") (pintype "input"))
      (node (ref "U12") (pin "12") (pinfunction "VM_12") (pintype "power_in"))
      (node (ref "U2") (pin "8") (pinfunction "V+_8") (pintype "power_in"))
      (node (ref "U5") (pin "3") (pinfunction "IN_3") (pintype "passive"))
      (node (ref "U9") (pin "1") (pinfunction "NSLEEP_1") (pintype "input"))
      (node (ref "U9") (pin "12") (pinfunction "VM_12") (pintype "power_in"))
    )
    (net (code "84") (name "VLEDS") (class "Default")
      (node (ref "C13") (pin "1") (pinfunction "1_1") (pintype "passive"))
      (node (ref "C14") (pin "1") (pinfunction "1_1") (pintype "passive"))
      (node (ref "C15") (pin "1") (pinfunction "1_1") (pintype "passive"))
      (node (ref "C16") (pin "1") (pinfunction "1_1") (pintype "passive"))
      (node (ref "D1") (pin "2") (pinfunction "A_2") (pintype "passive"))
      (node (ref "JTOP") (pin "7") (pinfunction "7_7") (pintype "power_in"))
      (node (ref "ULED_OUTER1") (pin "1") (pinfunction "VDD_1") (pintype "power_in"))
      (node (ref "ULED_OUTER2") (pin "1") (pinfunction "VDD_1") (pintype "power_in"))
      (node (ref "ULED_OUTER3") (pin "1") (pinfunction "VDD_1") (pintype "power_in"))
      (node (ref "ULED_OUTER4") (pin "1") (pinfunction "VDD_1") (pintype "power_in"))
    )
    (net (code "85") (name "unconnected-(B1-Pad4)") (class "Default")
      (node (ref "B1") (pin "4") (pintype "passive+no_connect"))
    )
    (net (code "86") (name "unconnected-(C47-Pad1)") (class "Default")
      (node (ref "C47") (pin "1") (pinfunction "1_1") (pintype "passive"))
    )
    (net (code "87") (name "unconnected-(Q1-PadD)") (class "Default")
      (node (ref "Q1") (pin "D") (pinfunction "D_D") (pintype "passive"))
    )
    (net (code "88") (name "unconnected-(Q1-PadG)") (class "Default")
      (node (ref "Q1") (pin "G") (pinfunction "G_G") (pintype "passive"))
    )
    (net (code "89") (name "unconnected-(Q1-PadS)") (class "Default")
      (node (ref "Q1") (pin "S") (pinfunction "S_S") (pintype "passive"))
    )
    (net (code "90") (name "unconnected-(U1-PC7_(TOSC2{slash}PCINT23)-Pad26)") (class "Default")
      (node (ref "U1") (pin "26") (pinfunction "PC7_(TOSC2/PCINT23)_26") (pintype "bidirectional+no_connect"))
    )
    (net (code "91") (name "unconnected-(U3-HOLD_(IO3)-Pad7)") (class "Default")
      (node (ref "U3") (pin "7") (pinfunction "HOLD_(IO3)_7") (pintype "passive+no_connect"))
    )
    (net (code "92") (name "unconnected-(U3-WP_(IO2)-Pad3)") (class "Default")
      (node (ref "U3") (pin "3") (pinfunction "WP_(IO2)_3") (pintype "passive+no_connect"))
    )
    (net (code "93") (name "unconnected-(U4-CS-Pad5)") (class "Default")
      (node (ref "U4") (pin "5") (pinfunction "CS_5") (pintype "passive"))
    )
    (net (code "94") (name "unconnected-(U4-DRDY{slash}INT2-Pad6)") (class "Default")
      (node (ref "U4") (pin "6") (pinfunction "DRDY/INT2_6") (pintype "passive"))
    )
    (net (code "95") (name "unconnected-(U4-GND-Pad13)") (class "Default")
      (node (ref "U4") (pin "13") (pinfunction "GND_13") (pintype "passive"))
    )
    (net (code "96") (name "unconnected-(U4-INT-Pad7)") (class "Default")
      (node (ref "U4") (pin "7") (pinfunction "INT_7") (pintype "passive"))
    )
    (net (code "97") (name "unconnected-(U4-PLLFILT-Pad14)") (class "Default")
      (node (ref "U4") (pin "14") (pinfunction "PLLFILT_14") (pintype "passive"))
    )
    (net (code "98") (name "unconnected-(U4-RES-Pad8)") (class "Default")
      (node (ref "U4") (pin "8") (pinfunction "RES_8") (pintype "passive"))
    )
    (net (code "99") (name "unconnected-(U4-RES-Pad9)") (class "Default")
      (node (ref "U4") (pin "9") (pinfunction "RES_9") (pintype "passive"))
    )
    (net (code "100") (name "unconnected-(U4-RES-Pad10)") (class "Default")
      (node (ref "U4") (pin "10") (pinfunction "RES_10") (pintype "passive"))
    )
    (net (code "101") (name "unconnected-(U4-RES-Pad11)") (class "Default")
      (node (ref "U4") (pin "11") (pinfunction "RES_11") (pintype "passive"))
    )
    (net (code "102") (name "unconnected-(U4-RES-Pad12)") (class "Default")
      (node (ref "U4") (pin "12") (pinfunction "RES_12") (pintype "passive"))
    )
    (net (code "103") (name "unconnected-(U4-RES-Pad15)") (class "Default")
      (node (ref "U4") (pin "15") (pinfunction "RES_15") (pintype "passive"))
    )
    (net (code "104") (name "unconnected-(U4-SCL{slash}SPC-Pad2)") (class "Default")
      (node (ref "U4") (pin "2") (pinfunction "SCL/SPC_2") (pintype "passive"))
    )
    (net (code "105") (name "unconnected-(U4-SDA{slash}SDI{slash}SDO-Pad3)") (class "Default")
      (node (ref "U4") (pin "3") (pinfunction "SDA/SDI/SDO_3") (pintype "passive"))
    )
    (net (code "106") (name "unconnected-(U4-SDO{slash}SA0-Pad4)") (class "Default")
      (node (ref "U4") (pin "4") (pinfunction "SDO/SA0_4") (pintype "passive"))
    )
    (net (code "107") (name "unconnected-(U4-Vdd-Pad16)") (class "Default")
      (node (ref "U4") (pin "16") (pinfunction "Vdd_16") (pintype "passive"))
    )
    (net (code "108") (name "unconnected-(U4-Vdd_IO-Pad1)") (class "Default")
      (node (ref "U4") (pin "1") (pinfunction "Vdd_IO_1") (pintype "passive"))
    )
    (net (code "109") (name "unconnected-(U9-BOUT1-Pad7)") (class "Default")
      (node (ref "U9") (pin "7") (pinfunction "BOUT1_7") (pintype "power_in+no_connect"))
    )
    (net (code "110") (name "unconnected-(U9-BOUT2-Pad5)") (class "Default")
      (node (ref "U9") (pin "5") (pinfunction "BOUT2_5") (pintype "power_in+no_connect"))
    )
    (net (code "111") (name "unconnected-(U9-NFAULT-Pad8)") (class "Default")
      (node (ref "U9") (pin "8") (pinfunction "NFAULT_8") (pintype "output+no_connect"))
    )
    (net (code "112") (name "unconnected-(U12-NFAULT-Pad8)") (class "Default")
      (node (ref "U12") (pin "8") (pinfunction "NFAULT_8") (pintype "output+no_connect"))
    )
    (net (code "113") (name "unconnected-(ULED_OUTER4-DOUT-Pad2)") (class "Default")
      (node (ref "ULED_OUTER4") (pin "2") (pinfunction "DOUT_2") (pintype "output+no_connect"))
    )
    (net (code "114") (name "unconnected-(URFID-AUX1-Pad19)") (class "Default")
      (node (ref "URFID") (pin "19") (pinfunction "AUX1_19") (pintype "passive+no_connect"))
    )
    (net (code "115") (name "unconnected-(URFID-AUX2-Pad20)") (class "Default")
      (node (ref "URFID") (pin "20") (pinfunction "AUX2_20") (pintype "passive+no_connect"))
    )
    (net (code "116") (name "unconnected-(URFID-D1-Pad25)") (class "Default")
      (node (ref "URFID") (pin "25") (pinfunction "D1_25") (pintype "passive+no_connect"))
    )
    (net (code "117") (name "unconnected-(URFID-D2-Pad26)") (class "Default")
      (node (ref "URFID") (pin "26") (pinfunction "D2_26") (pintype "passive+no_connect"))
    )
    (net (code "118") (name "unconnected-(URFID-D3-Pad27)") (class "Default")
      (node (ref "URFID") (pin "27") (pinfunction "D3_27") (pintype "passive+no_connect"))
    )
    (net (code "119") (name "unconnected-(URFID-D4-Pad28)") (class "Default")
      (node (ref "URFID") (pin "28") (pinfunction "D4_28") (pintype "passive+no_connect"))
    )
    (net (code "120") (name "unconnected-(URFID-MFIN-Pad7)") (class "Default")
      (node (ref "URFID") (pin "7") (pinfunction "MFIN_7") (pintype "passive+no_connect"))
    )
    (net (code "121") (name "unconnected-(URFID-MFOUT-Pad8)") (class "Default")
      (node (ref "URFID") (pin "8") (pinfunction "MFOUT_8") (pintype "passive+no_connect"))
    )
    (net (code "122") (name "unconnected-(URFID-SVDD-Pad9)") (class "Default")
      (node (ref "URFID") (pin "9") (pinfunction "SVDD_9") (pintype "passive+no_connect"))
    )
  )
)
